# CON-USB.net
KiCad netlist of a schematic drawn in Altium Designer
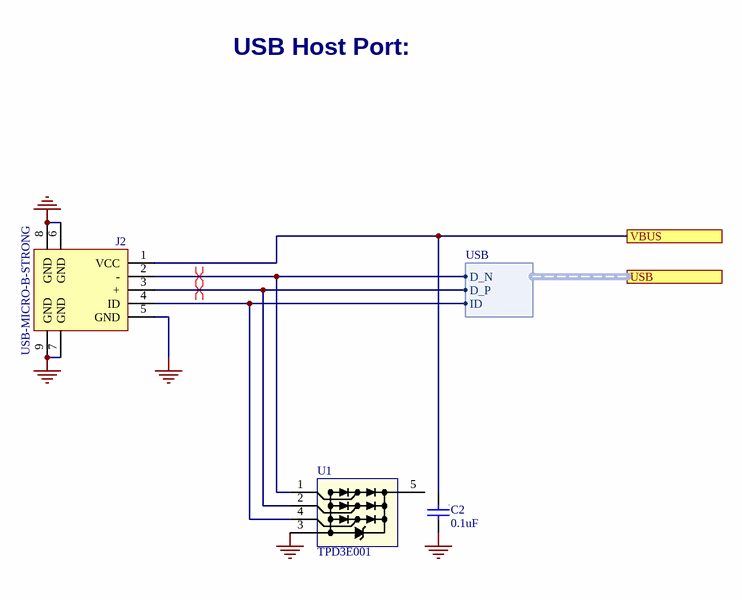
[diagram p0: CON-USB.SchDoc]

(export (version "E")
  (design (tool "Eeschema 10.0.6"))
  (components
    (comp (ref "C2")
      (value "0.1uF")
      (footprint "0402")
      (description "CAP CER .10UF 50V X7R 10% 0402")
      (fields
        (field (name "MANUFACTURER") "TDK Corporation")
        (field (name "MANUFACTURER PART NUMBER") "C1005X7R1H104K")
        (field (name "PUBLISHER") "Altium Limited")
      )
      (libsource (lib "General") (part "Cap"))
    )
    (comp (ref "J2")
      (value "USB-MICRO-B-STRONG")
      (footprint "USB Micro AB R/A THR - design")
      (description "CONN USB MICRO B RECPT SMT R/A")
      (fields
        (field (name "MANUFACTURER") "Amphenol FCI")
        (field (name "MANUFACTURER PART NUMBER") "10118194-0001LF")
      )
      (libsource (lib "Connectors") (part "USB-TYPEAB-4GND"))
    )
    (comp (ref "U1")
      (value "TPD3E001")
      (footprint "SOTFL50P160X60-5N")
      (description "TVS DIODE 5.5V SOT5")
      (fields
        (field (name "MANUFACTURER") "Texas Instruments")
        (field (name "MANUFACTURER PART NUMBER") "TPD3E001DRLR")
      )
      (libsource (lib "ICs") (part "TPD3E001"))
    )
  )
  (nets
    (net (code "2") (name "/VBUS") (class "Default")
      (node (ref "C2") (pin "1") (pinfunction "1_1") (pintype "passive"))
      (node (ref "J2") (pin "1") (pinfunction "VCC_1") (pintype "passive"))
    )
    (net (code "4") (name "GND") (class "Default")
      (node (ref "C2") (pin "2") (pinfunction "2_2") (pintype "passive"))
      (node (ref "J2") (pin "5") (pinfunction "GND_5") (pintype "passive"))
      (node (ref "J2") (pin "6") (pinfunction "GND_6") (pintype "passive"))
      (node (ref "J2") (pin "7") (pinfunction "GND_7") (pintype "passive"))
      (node (ref "J2") (pin "8") (pinfunction "GND_8") (pintype "passive"))
      (node (ref "J2") (pin "9") (pinfunction "GND_9") (pintype "passive"))
      (node (ref "U1") (pin "3") (pintype "passive"))
    )
    (net (code "5") (name "Net-(J2-+)") (class "Default")
      (node (ref "J2") (pin "3") (pinfunction "+_3") (pintype "passive"))
      (node (ref "U1") (pin "2") (pintype "passive"))
    )
    (net (code "6") (name "Net-(J2--)") (class "Default")
      (node (ref "J2") (pin "2") (pinfunction "-_2") (pintype "passive"))
      (node (ref "U1") (pin "1") (pintype "passive"))
    )
    (net (code "7") (name "Net-(J2-ID)") (class "Default")
      (node (ref "J2") (pin "4") (pinfunction "ID_4") (pintype "passive"))
      (node (ref "U1") (pin "4") (pinfunction "nc_4") (pintype "passive"))
    )
    (net (code "8") (name "unconnected-(U1-nc-Pad5)") (class "Default")
      (node (ref "U1") (pin "5") (pinfunction "nc_5") (pintype "passive"))
    )
  )
)
